# Power_4.net
KiCad netlist of a schematic drawn in Altium Designer
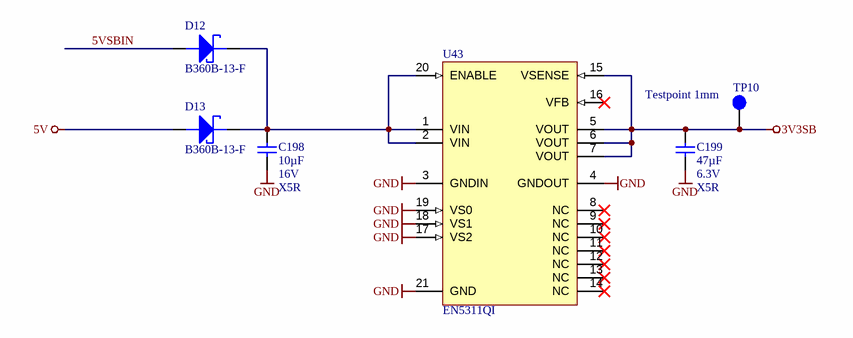
[diagram p0: Power_4.schdoc]

(export (version "E")
  (design (tool "Eeschema 10.0.6"))
  (components
    (comp (ref "C198")
      (value "10µF")
      (footprint "CAPC1608X90N")
      (description "KON 10µF 16V X5R SMD 20%")
      (fields
        (field (name "VOLTAGE") "16V")
        (field (name "TECHNOLOGY") "X5R")
        (field (name "TOLERANCE") "20%")
      )
      (libsource (lib "TE") (part "CAP-NP"))
    )
    (comp (ref "C199")
      (value "47µF")
      (footprint "CAPC3216X180N")
      (description "KON 47µF 6.3V  X5R SMD 20%")
      (fields
        (field (name "VOLTAGE") "6.3V")
        (field (name "TECHNOLOGY") "X5R")
        (field (name "TOLERANCE") "20%")
      )
      (libsource (lib "TE") (part "CAP-NP"))
    )
    (comp (ref "D12")
      (value "B360B-13-F")
      (footprint "DIOM4336X250N")
      (description "B360B-13-F SMD")
      (libsource (lib "TE") (part "SCHOTTKY"))
    )
    (comp (ref "D13")
      (value "B360B-13-F")
      (footprint "DIOM4336X250N")
      (description "B360B-13-F SMD")
      (libsource (lib "TE") (part "SCHOTTKY"))
    )
    (comp (ref "TP10") (value "Testpoint 1mm") (footprint "TP_1mm") (libsource (lib "TE") (part "TP")))
    (comp (ref "U43") (value "EN5311QI") (footprint "EN5311QI") (libsource (lib "TE") (part "EN5311QI")))
  )
  (nets
    (net (code "1") (name "/5VSBIN") (class "Default")
      (node (ref "D12") (pin "2") (pinfunction "ANODE_2") (pintype "passive"))
    )
    (net (code "2") (name "3V3SB") (class "Default")
      (node (ref "C199") (pin "1") (pinfunction "1_1") (pintype "passive"))
      (node (ref "TP10") (pin "1") (pintype "passive"))
      (node (ref "U43") (pin "15") (pinfunction "VSENSE_15") (pintype "input"))
      (node (ref "U43") (pin "5") (pinfunction "VOUT_5") (pintype "power_in"))
      (node (ref "U43") (pin "6") (pinfunction "VOUT_6") (pintype "power_in"))
      (node (ref "U43") (pin "7") (pinfunction "VOUT_7") (pintype "power_in"))
    )
    (net (code "3") (name "5V") (class "Default")
      (node (ref "D13") (pin "2") (pinfunction "ANODE_2") (pintype "passive"))
    )
    (net (code "4") (name "GND") (class "Default")
      (node (ref "C198") (pin "2") (pinfunction "2_2") (pintype "passive"))
      (node (ref "C199") (pin "2") (pinfunction "2_2") (pintype "passive"))
      (node (ref "U43") (pin "17") (pinfunction "VS2_17") (pintype "input"))
      (node (ref "U43") (pin "18") (pinfunction "VS1_18") (pintype "input"))
      (node (ref "U43") (pin "19") (pinfunction "VS0_19") (pintype "input"))
      (node (ref "U43") (pin "21") (pinfunction "GND_21") (pintype "power_in"))
      (node (ref "U43") (pin "3") (pinfunction "GNDIN_3") (pintype "power_in"))
      (node (ref "U43") (pin "4") (pinfunction "GNDOUT_4") (pintype "power_in"))
    )
    (net (code "5") (name "Net-(D12-KATHODE)") (class "Default")
      (node (ref "C198") (pin "1") (pinfunction "1_1") (pintype "passive"))
      (node (ref "D12") (pin "1") (pinfunction "KATHODE_1") (pintype "passive"))
      (node (ref "D13") (pin "1") (pinfunction "KATHODE_1") (pintype "passive"))
      (node (ref "U43") (pin "1") (pinfunction "VIN_1") (pintype "power_in"))
      (node (ref "U43") (pin "2") (pinfunction "VIN_2") (pintype "power_in"))
      (node (ref "U43") (pin "20") (pinfunction "ENABLE_20") (pintype "input"))
    )
    (net (code "6") (name "unconnected-(U43-NC-Pad8)") (class "Default")
      (node (ref "U43") (pin "8") (pinfunction "NC_8") (pintype "passive+no_connect"))
    )
    (net (code "7") (name "unconnected-(U43-NC-Pad9)") (class "Default")
      (node (ref "U43") (pin "9") (pinfunction "NC_9") (pintype "passive+no_connect"))
    )
    (net (code "8") (name "unconnected-(U43-NC-Pad10)") (class "Default")
      (node (ref "U43") (pin "10") (pinfunction "NC_10") (pintype "passive+no_connect"))
    )
    (net (code "9") (name "unconnected-(U43-NC-Pad11)") (class "Default")
      (node (ref "U43") (pin "11") (pinfunction "NC_11") (pintype "passive+no_connect"))
    )
    (net (code "10") (name "unconnected-(U43-NC-Pad12)") (class "Default")
      (node (ref "U43") (pin "12") (pinfunction "NC_12") (pintype "passive+no_connect"))
    )
    (net (code "11") (name "unconnected-(U43-NC-Pad13)") (class "Default")
      (node (ref "U43") (pin "13") (pinfunction "NC_13") (pintype "passive+no_connect"))
    )
    (net (code "12") (name "unconnected-(U43-NC-Pad14)") (class "Default")
      (node (ref "U43") (pin "14") (pinfunction "NC_14") (pintype "passive+no_connect"))
    )
    (net (code "13") (name "unconnected-(U43-VFB-Pad16)") (class "Default")
      (node (ref "U43") (pin "16") (pinfunction "VFB_16") (pintype "input+no_connect"))
    )
  )
)
